# talking_clock_V1.net
KiCad netlist of a schematic drawn in EAGLE
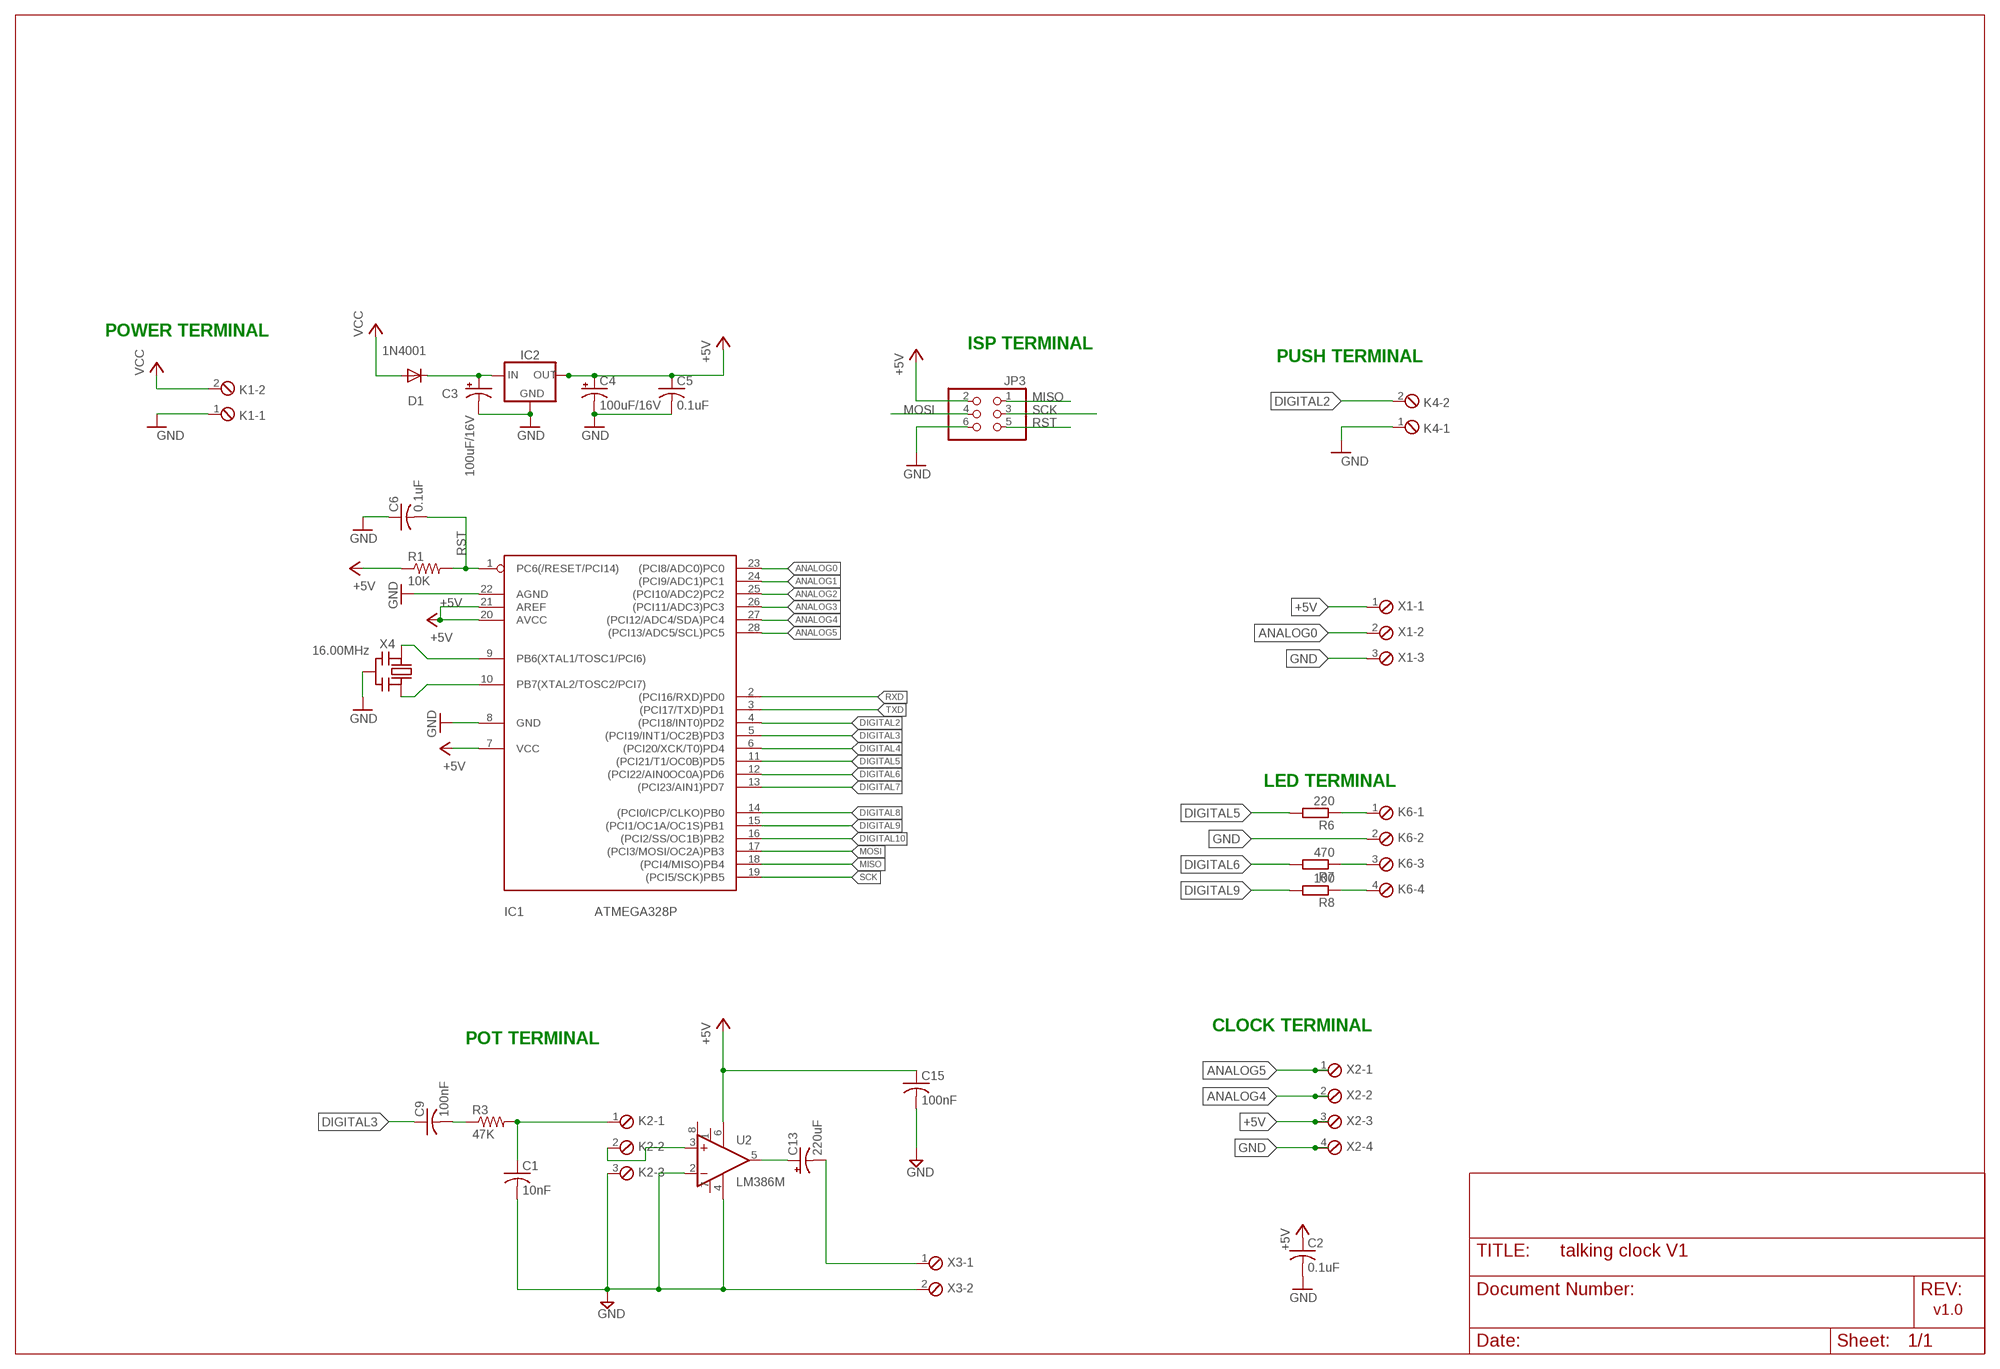
[diagram p0: schematic, sheet 1]

(export (version "E")
  (design (tool "Eeschema 10.0.6"))
  (components
    (comp (ref "C1")
      (value "10nF")
      (footprint "eagle-import:C050-025X075")
      (libsource (lib "eagle-import") (part "rcl_C-US050-025X075"))
    )
    (comp (ref "C2")
      (value "0.1uF")
      (footprint "eagle-import:C025-025X050")
      (libsource (lib "eagle-import") (part "C-US025-025X050"))
    )
    (comp (ref "C3")
      (value "100uF/16V")
      (footprint "eagle-import:E2,5-6")
      (libsource (lib "eagle-import") (part "CPOL-USE2.5-6"))
    )
    (comp (ref "C4")
      (value "100uF/16V")
      (footprint "eagle-import:E2,5-6")
      (libsource (lib "eagle-import") (part "CPOL-USE2.5-6"))
    )
    (comp (ref "C5")
      (value "0.1uF")
      (footprint "eagle-import:C025-025X050")
      (libsource (lib "eagle-import") (part "C-US025-025X050"))
    )
    (comp (ref "C6")
      (value "0.1uF")
      (footprint "eagle-import:C025-025X050")
      (libsource (lib "eagle-import") (part "C-US025-025X050"))
    )
    (comp (ref "C9")
      (value "100nF")
      (footprint "eagle-import:C025-025X050")
      (libsource (lib "eagle-import") (part "rcl_C-US025-025X050"))
    )
    (comp (ref "C13")
      (value "220uF")
      (footprint "eagle-import:E3,5-10")
      (libsource (lib "eagle-import") (part "rcl_CPOL-USE3.5-10"))
    )
    (comp (ref "C15")
      (value "100nF")
      (footprint "eagle-import:C025-025X050")
      (libsource (lib "eagle-import") (part "rcl_C-US025-025X050"))
    )
    (comp (ref "D1")
      (value "1N4001")
      (footprint "eagle-import:DO41-10")
      (libsource (lib "eagle-import") (part "1N4004"))
    )
    (comp (ref "IC1")
      (value "ATMEGA328P")
      (footprint "eagle-import:DIL28_3")
      (libsource (lib "eagle-import") (part "ATMEGA168PROUND"))
    )
    (comp (ref "IC2")
      (value "78L05")
      (footprint "eagle-import:78XXS")
      (libsource (lib "eagle-import") (part "78XXS"))
    )
    (comp (ref "JP3")
      (value "PINHD-2X3")
      (footprint "eagle-import:2X03")
      (libsource (lib "eagle-import") (part "PINHD-2X3"))
    )
    (comp (ref "K1")
      (value "MPT2")
      (footprint "eagle-import:2POL254")
      (fields (field (name "OC_FARNELL") "unknown") (field (name "OC_NEWARK") "unknown"))
      (libsource (lib "eagle-import") (part "MPT2"))
    )
    (comp (ref "K2")
      (value "MPT3")
      (footprint "eagle-import:3POL254")
      (libsource (lib "eagle-import") (part "MPT3"))
    )
    (comp (ref "K4")
      (value "MPT2")
      (footprint "eagle-import:2POL254")
      (fields (field (name "OC_FARNELL") "unknown") (field (name "OC_NEWARK") "unknown"))
      (libsource (lib "eagle-import") (part "MPT2"))
    )
    (comp (ref "K6")
      (value "MPT4")
      (footprint "eagle-import:4POL254")
      (fields (field (name "OC_FARNELL") "unknown") (field (name "OC_NEWARK") "unknown"))
      (libsource (lib "eagle-import") (part "MPT4"))
    )
    (comp (ref "R1")
      (value "10K")
      (footprint "eagle-import:0207_10")
      (libsource (lib "eagle-import") (part "rcl-ez_R-US_0207/10"))
    )
    (comp (ref "R3")
      (value "47K")
      (footprint "eagle-import:0207_10")
      (libsource (lib "eagle-import") (part "R-US_0207/10"))
    )
    (comp (ref "R6")
      (value "220")
      (footprint "eagle-import:0207_10")
      (libsource (lib "eagle-import") (part "R-EU_0207/10"))
    )
    (comp (ref "R7")
      (value "470")
      (footprint "eagle-import:0207_10")
      (libsource (lib "eagle-import") (part "R-EU_0207/10"))
    )
    (comp (ref "R8")
      (value "100")
      (footprint "eagle-import:0207_10")
      (libsource (lib "eagle-import") (part "R-EU_0207/10"))
    )
    (comp (ref "U2")
      (value "LM386M")
      (footprint "eagle-import:SO08")
      (libsource (lib "eagle-import") (part "LM386M"))
    )
    (comp (ref "X1")
      (value "MPT3")
      (footprint "eagle-import:3POL254")
      (libsource (lib "eagle-import") (part "MPT3"))
    )
    (comp (ref "X2")
      (value "MPT4")
      (footprint "eagle-import:4POL254")
      (libsource (lib "eagle-import") (part "MPT4"))
    )
    (comp (ref "X3")
      (value "MPT2")
      (footprint "eagle-import:2POL254")
      (libsource (lib "eagle-import") (part "MPT2"))
    )
    (comp (ref "X4")
      (value "16.00MHz")
      (footprint "eagle-import:CERM_OSC")
      (libsource (lib "eagle-import") (part "CERMOSCILL"))
    )
  )
  (nets
    (net (code "1") (name "+5V") (class "Default")
      (node (ref "C15") (pin "1") (pinfunction "1_1") (pintype "passive"))
      (node (ref "C2") (pin "1") (pinfunction "1_1") (pintype "passive"))
      (node (ref "C4") (pin "+") (pinfunction "+_+") (pintype "passive"))
      (node (ref "C5") (pin "1") (pinfunction "1_1") (pintype "passive"))
      (node (ref "IC1") (pin "20") (pinfunction "AVCC_20") (pintype "bidirectional"))
      (node (ref "IC1") (pin "21") (pinfunction "AREF_21") (pintype "bidirectional"))
      (node (ref "IC1") (pin "7") (pinfunction "VCC_7") (pintype "bidirectional"))
      (node (ref "IC2") (pin "OUT") (pinfunction "OUT_OUT") (pintype "passive"))
      (node (ref "JP3") (pin "2") (pinfunction "2_2") (pintype "passive"))
      (node (ref "R1") (pin "1") (pinfunction "1_1") (pintype "passive"))
      (node (ref "U2") (pin "6") (pinfunction "V+_6") (pintype "power_in"))
      (node (ref "X1") (pin "1") (pinfunction "1_1") (pintype "passive"))
      (node (ref "X2") (pin "3") (pinfunction "1_3") (pintype "passive"))
    )
    (net (code "2") (name "/RST") (class "Default")
      (node (ref "C6") (pin "2") (pinfunction "2_2") (pintype "passive"))
      (node (ref "IC1") (pin "1") (pinfunction "PC6(/RESET/PCI14)_1") (pintype "bidirectional"))
      (node (ref "JP3") (pin "5") (pinfunction "5_5") (pintype "passive"))
      (node (ref "R1") (pin "2") (pinfunction "2_2") (pintype "passive"))
    )
    (net (code "3") (name "ANALOG0") (class "Default")
      (node (ref "IC1") (pin "23") (pinfunction "(PCI8/ADC0)PC0_23") (pintype "bidirectional"))
      (node (ref "X1") (pin "2") (pinfunction "1_2") (pintype "passive"))
    )
    (net (code "4") (name "ANALOG1") (class "Default")
      (node (ref "IC1") (pin "24") (pinfunction "(PCI9/ADC1)PC1_24") (pintype "bidirectional"))
    )
    (net (code "5") (name "ANALOG2") (class "Default")
      (node (ref "IC1") (pin "25") (pinfunction "(PCI10/ADC2)PC2_25") (pintype "bidirectional"))
    )
    (net (code "6") (name "ANALOG3") (class "Default")
      (node (ref "IC1") (pin "26") (pinfunction "(PCI11/ADC3)PC3_26") (pintype "bidirectional"))
    )
    (net (code "7") (name "ANALOG4") (class "Default")
      (node (ref "IC1") (pin "27") (pinfunction "(PCI12/ADC4/SDA)PC4_27") (pintype "bidirectional"))
      (node (ref "X2") (pin "2") (pinfunction "1_2") (pintype "passive"))
    )
    (net (code "8") (name "ANALOG5") (class "Default")
      (node (ref "IC1") (pin "28") (pinfunction "(PCI13/ADC5/SCL)PC5_28") (pintype "bidirectional"))
      (node (ref "X2") (pin "1") (pinfunction "1_1") (pintype "passive"))
    )
    (net (code "9") (name "DIGITAL2") (class "Default")
      (node (ref "IC1") (pin "4") (pinfunction "(PCI18/INT0)PD2_4") (pintype "bidirectional"))
      (node (ref "K4") (pin "2") (pinfunction "1_2") (pintype "passive"))
    )
    (net (code "10") (name "DIGITAL3") (class "Default")
      (node (ref "C9") (pin "1") (pinfunction "1_1") (pintype "passive"))
      (node (ref "IC1") (pin "5") (pinfunction "(PCI19/INT1/OC2B)PD3_5") (pintype "bidirectional"))
    )
    (net (code "11") (name "DIGITAL4") (class "Default")
      (node (ref "IC1") (pin "6") (pinfunction "(PCI20/XCK/T0)PD4_6") (pintype "bidirectional"))
    )
    (net (code "12") (name "DIGITAL5") (class "Default")
      (node (ref "IC1") (pin "11") (pinfunction "(PCI21/T1/OC0B)PD5_11") (pintype "bidirectional"))
      (node (ref "R6") (pin "2") (pinfunction "2_2") (pintype "passive"))
    )
    (net (code "13") (name "DIGITAL6") (class "Default")
      (node (ref "IC1") (pin "12") (pinfunction "(PCI22/AIN0OC0A)PD6_12") (pintype "bidirectional"))
      (node (ref "R7") (pin "2") (pinfunction "2_2") (pintype "passive"))
    )
    (net (code "14") (name "DIGITAL7") (class "Default")
      (node (ref "IC1") (pin "13") (pinfunction "(PCI23/AIN1)PD7_13") (pintype "bidirectional"))
    )
    (net (code "15") (name "DIGITAL8") (class "Default")
      (node (ref "IC1") (pin "14") (pinfunction "(PCI0/ICP/CLKO)PB0_14") (pintype "bidirectional"))
    )
    (net (code "16") (name "DIGITAL9") (class "Default")
      (node (ref "IC1") (pin "15") (pinfunction "(PCI1/OC1A/OC1S)PB1_15") (pintype "bidirectional"))
      (node (ref "R8") (pin "2") (pinfunction "2_2") (pintype "passive"))
    )
    (net (code "17") (name "DIGITAL10") (class "Default")
      (node (ref "IC1") (pin "16") (pinfunction "(PCI2/SS/OC1B)PB2_16") (pintype "bidirectional"))
    )
    (net (code "18") (name "GND") (class "Default")
      (node (ref "C1") (pin "2") (pinfunction "2_2") (pintype "passive"))
      (node (ref "C15") (pin "2") (pinfunction "2_2") (pintype "passive"))
      (node (ref "C2") (pin "2") (pinfunction "2_2") (pintype "passive"))
      (node (ref "C3") (pin "-") (pinfunction "-_-") (pintype "passive"))
      (node (ref "C4") (pin "-") (pinfunction "-_-") (pintype "passive"))
      (node (ref "C5") (pin "2") (pinfunction "2_2") (pintype "passive"))
      (node (ref "C6") (pin "1") (pinfunction "1_1") (pintype "passive"))
      (node (ref "IC1") (pin "22") (pinfunction "AGND_22") (pintype "bidirectional"))
      (node (ref "IC1") (pin "8") (pinfunction "GND_8") (pintype "bidirectional"))
      (node (ref "IC2") (pin "GND") (pinfunction "GND_GND") (pintype "input"))
      (node (ref "JP3") (pin "6") (pinfunction "6_6") (pintype "passive"))
      (node (ref "K1") (pin "1") (pinfunction "1_1") (pintype "passive"))
      (node (ref "K2") (pin "3") (pinfunction "1_3") (pintype "passive"))
      (node (ref "K4") (pin "1") (pinfunction "1_1") (pintype "passive"))
      (node (ref "K6") (pin "2") (pinfunction "1_2") (pintype "passive"))
      (node (ref "U2") (pin "2") (pinfunction "-IN_2") (pintype "input"))
      (node (ref "U2") (pin "4") (pinfunction "V-_4") (pintype "power_in"))
      (node (ref "X1") (pin "3") (pinfunction "1_3") (pintype "passive"))
      (node (ref "X2") (pin "4") (pinfunction "1_4") (pintype "passive"))
      (node (ref "X3") (pin "2") (pinfunction "1_2") (pintype "passive"))
      (node (ref "X4") (pin "P$2") (pinfunction "GND_P$2") (pintype "bidirectional"))
    )
    (net (code "19") (name "MISO") (class "Default")
      (node (ref "IC1") (pin "18") (pinfunction "(PCI4/MISO)PB4_18") (pintype "bidirectional"))
      (node (ref "JP3") (pin "1") (pinfunction "1_1") (pintype "passive"))
    )
    (net (code "20") (name "MOSI") (class "Default")
      (node (ref "IC1") (pin "17") (pinfunction "(PCI3/MOSI/OC2A)PB3_17") (pintype "bidirectional"))
      (node (ref "JP3") (pin "4") (pinfunction "4_4") (pintype "passive"))
    )
    (net (code "21") (name "Net-(C1-Pad1)") (class "Default")
      (node (ref "C1") (pin "1") (pinfunction "1_1") (pintype "passive"))
      (node (ref "K2") (pin "1") (pinfunction "1_1") (pintype "passive"))
      (node (ref "R3") (pin "2") (pinfunction "2_2") (pintype "passive"))
    )
    (net (code "22") (name "Net-(C3-Pad+)") (class "Default")
      (node (ref "C3") (pin "+") (pinfunction "+_+") (pintype "passive"))
      (node (ref "D1") (pin "C") (pinfunction "C_C") (pintype "passive"))
      (node (ref "IC2") (pin "IN") (pinfunction "IN_IN") (pintype "input"))
    )
    (net (code "23") (name "Net-(C9-Pad2)") (class "Default")
      (node (ref "C9") (pin "2") (pinfunction "2_2") (pintype "passive"))
      (node (ref "R3") (pin "1") (pinfunction "1_1") (pintype "passive"))
    )
    (net (code "24") (name "Net-(C13-Pad-)") (class "Default")
      (node (ref "C13") (pin "-") (pinfunction "-_-") (pintype "passive"))
      (node (ref "X3") (pin "1") (pinfunction "1_1") (pintype "passive"))
    )
    (net (code "25") (name "Net-(IC1-PB6(XTAL1{slash}TOSC1{slash}PCI6))") (class "Default")
      (node (ref "IC1") (pin "9") (pinfunction "PB6(XTAL1/TOSC1/PCI6)_9") (pintype "bidirectional"))
      (node (ref "X4") (pin "P$1") (pinfunction "IN_P$1") (pintype "bidirectional"))
    )
    (net (code "26") (name "Net-(IC1-PB7(XTAL2{slash}TOSC2{slash}PCI7))") (class "Default")
      (node (ref "IC1") (pin "10") (pinfunction "PB7(XTAL2/TOSC2/PCI7)_10") (pintype "bidirectional"))
      (node (ref "X4") (pin "P$3") (pinfunction "OUT_P$3") (pintype "bidirectional"))
    )
    (net (code "27") (name "Net-(K2B-1)") (class "Default")
      (node (ref "K2") (pin "2") (pinfunction "1_2") (pintype "passive"))
      (node (ref "U2") (pin "3") (pinfunction "+IN_3") (pintype "input"))
    )
    (net (code "28") (name "Net-(K6-Pad1)") (class "Default")
      (node (ref "K6") (pin "1") (pinfunction "1_1") (pintype "passive"))
      (node (ref "R6") (pin "1") (pinfunction "1_1") (pintype "passive"))
    )
    (net (code "29") (name "Net-(K6C-1)") (class "Default")
      (node (ref "K6") (pin "3") (pinfunction "1_3") (pintype "passive"))
      (node (ref "R7") (pin "1") (pinfunction "1_1") (pintype "passive"))
    )
    (net (code "30") (name "Net-(K6D-1)") (class "Default")
      (node (ref "K6") (pin "4") (pinfunction "1_4") (pintype "passive"))
      (node (ref "R8") (pin "1") (pinfunction "1_1") (pintype "passive"))
    )
    (net (code "31") (name "Net-(U2-OUT)") (class "Default")
      (node (ref "C13") (pin "+") (pinfunction "+_+") (pintype "passive"))
      (node (ref "U2") (pin "5") (pinfunction "OUT_5") (pintype "output"))
    )
    (net (code "32") (name "RXD") (class "Default")
      (node (ref "IC1") (pin "2") (pinfunction "(PCI16/RXD)PD0_2") (pintype "bidirectional"))
    )
    (net (code "33") (name "SCK") (class "Default")
      (node (ref "IC1") (pin "19") (pinfunction "(PCI5/SCK)PB5_19") (pintype "bidirectional"))
      (node (ref "JP3") (pin "3") (pinfunction "3_3") (pintype "passive"))
    )
    (net (code "34") (name "TXD") (class "Default")
      (node (ref "IC1") (pin "3") (pinfunction "(PCI17/TXD)PD1_3") (pintype "bidirectional"))
    )
    (net (code "35") (name "VCC") (class "Default")
      (node (ref "D1") (pin "A") (pinfunction "A_A") (pintype "passive"))
      (node (ref "K1") (pin "2") (pinfunction "1_2") (pintype "passive"))
    )
    (net (code "36") (name "unconnected-(U2-BYPASS-Pad7)") (class "Default")
      (node (ref "U2") (pin "7") (pinfunction "BYPASS_7") (pintype "output"))
    )
    (net (code "37") (name "unconnected-(U2-GAIN+-Pad1)") (class "Default")
      (node (ref "U2") (pin "1") (pinfunction "GAIN+_1") (pintype "input"))
    )
    (net (code "38") (name "unconnected-(U2-GAIN--Pad8)") (class "Default")
      (node (ref "U2") (pin "8") (pinfunction "GAIN-_8") (pintype "input"))
    )
  )
)
